# dualAudio2GatewithCV.net
KiCad netlist of a schematic drawn in EAGLE
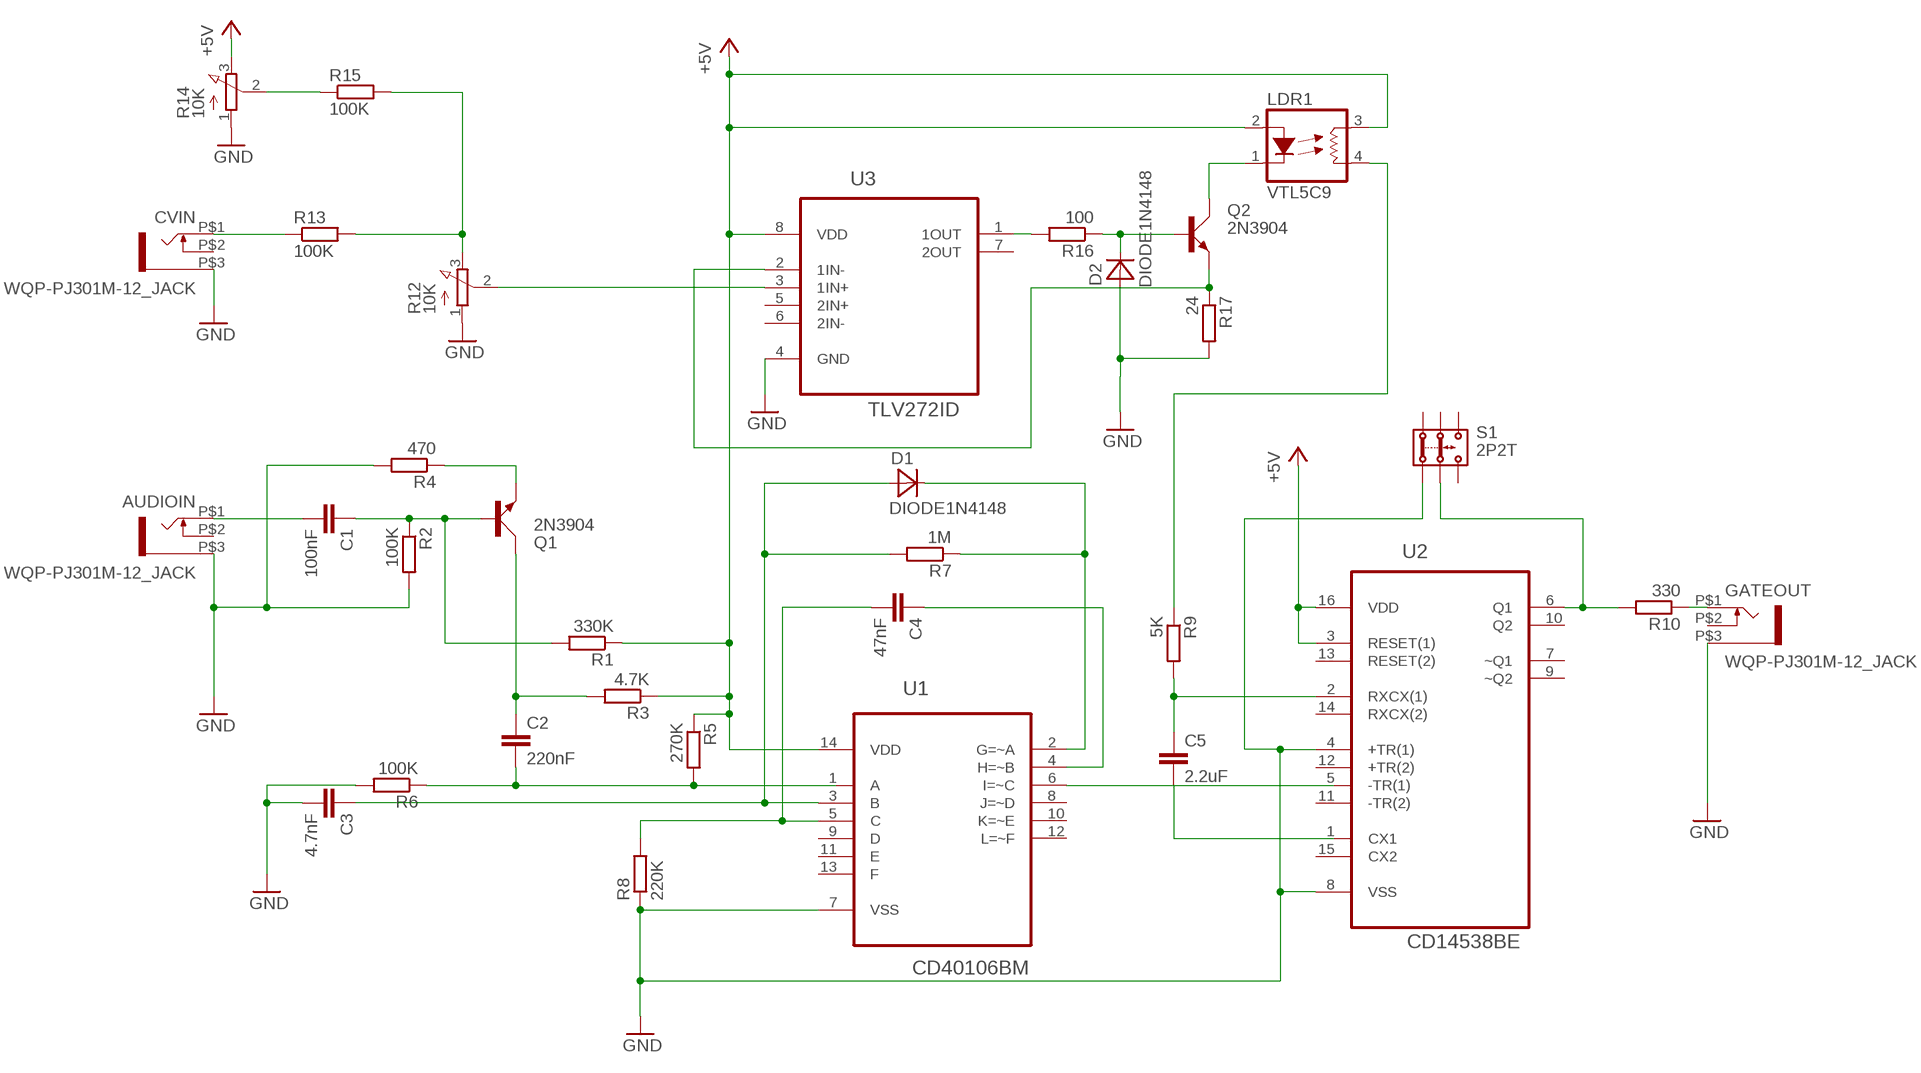
[diagram p0: schematic, sheet 1]

(export (version "E")
  (design (tool "Eeschema 10.0.6"))
  (components
    (comp (ref "AUDIOIN")
      (value "WQP-PJ301M-12_JACK")
      (footprint "eagle-import:WQP-PJ301M-12_JACK")
      (libsource (lib "eagle-import") (part "WQP-PJ301M-12_JACK"))
    )
    (comp (ref "C1")
      (value "100nF")
      (footprint "eagle-import:C025-025X050")
      (libsource (lib "eagle-import") (part "C-EU025-025X050"))
    )
    (comp (ref "C2")
      (value "220nF")
      (footprint "eagle-import:C025-025X050")
      (libsource (lib "eagle-import") (part "C-EU025-025X050"))
    )
    (comp (ref "C3")
      (value "4.7nF")
      (footprint "eagle-import:C025-025X050")
      (libsource (lib "eagle-import") (part "C-EU025-025X050"))
    )
    (comp (ref "C4")
      (value "47nF")
      (footprint "eagle-import:C025-025X050")
      (libsource (lib "eagle-import") (part "C-EU025-025X050"))
    )
    (comp (ref "C5")
      (value "2.2uF")
      (footprint "eagle-import:C025-025X050")
      (libsource (lib "eagle-import") (part "C-EU025-025X050"))
    )
    (comp (ref "CVIN")
      (value "WQP-PJ301M-12_JACK")
      (footprint "eagle-import:WQP-PJ301M-12_JACK")
      (libsource (lib "eagle-import") (part "WQP-PJ301M-12_JACK"))
    )
    (comp (ref "D1")
      (value "DIODE1N4148")
      (footprint "eagle-import:DO-35")
      (libsource (lib "eagle-import") (part "DIODE1N4148"))
    )
    (comp (ref "D2")
      (value "DIODE1N4148")
      (footprint "eagle-import:DO-35")
      (libsource (lib "eagle-import") (part "DIODE1N4148"))
    )
    (comp (ref "GATEOUT")
      (value "WQP-PJ301M-12_JACK")
      (footprint "eagle-import:WQP-PJ301M-12_JACK")
      (libsource (lib "eagle-import") (part "WQP-PJ301M-12_JACK"))
    )
    (comp (ref "LDR1")
      (value "VTL5C9")
      (footprint "eagle-import:VTL5C")
      (fields (field (name "MF") "VACTEC PHOTO"))
      (libsource (lib "eagle-import") (part "VTL5C9"))
    )
    (comp (ref "Q1")
      (value "2N3904")
      (footprint "eagle-import:TO92D")
      (libsource (lib "eagle-import") (part "2N3904"))
    )
    (comp (ref "Q2")
      (value "2N3904")
      (footprint "eagle-import:TO92D")
      (libsource (lib "eagle-import") (part "2N3904"))
    )
    (comp (ref "R1")
      (value "330K")
      (footprint "eagle-import:0204V")
      (libsource (lib "eagle-import") (part "R-EU_0204/2V"))
    )
    (comp (ref "R2")
      (value "100K")
      (footprint "eagle-import:0204V")
      (libsource (lib "eagle-import") (part "R-EU_0204/2V"))
    )
    (comp (ref "R3")
      (value "4.7K")
      (footprint "eagle-import:0204V")
      (libsource (lib "eagle-import") (part "R-EU_0204/2V"))
    )
    (comp (ref "R4")
      (value "470")
      (footprint "eagle-import:0204V")
      (libsource (lib "eagle-import") (part "R-EU_0204/2V"))
    )
    (comp (ref "R5")
      (value "270K")
      (footprint "eagle-import:0204V")
      (libsource (lib "eagle-import") (part "R-EU_0204/2V"))
    )
    (comp (ref "R6")
      (value "100K")
      (footprint "eagle-import:0204V")
      (libsource (lib "eagle-import") (part "R-EU_0204/2V"))
    )
    (comp (ref "R7")
      (value "1M")
      (footprint "eagle-import:0204V")
      (libsource (lib "eagle-import") (part "R-EU_0204/2V"))
    )
    (comp (ref "R8")
      (value "220K")
      (footprint "eagle-import:0204V")
      (libsource (lib "eagle-import") (part "R-EU_0204/2V"))
    )
    (comp (ref "R9")
      (value "5K")
      (footprint "eagle-import:0204V")
      (libsource (lib "eagle-import") (part "R-EU_0204/2V"))
    )
    (comp (ref "R10")
      (value "330")
      (footprint "eagle-import:0204V")
      (libsource (lib "eagle-import") (part "R-EU_0204/2V"))
    )
    (comp (ref "R12")
      (value "10K")
      (footprint "eagle-import:3RP_1610N")
      (libsource (lib "eagle-import") (part "3RP/1610N"))
    )
    (comp (ref "R13")
      (value "100K")
      (footprint "eagle-import:0204V")
      (libsource (lib "eagle-import") (part "R-EU_0204/2V"))
    )
    (comp (ref "R14")
      (value "10K")
      (footprint "eagle-import:3RP_1610N")
      (libsource (lib "eagle-import") (part "3RP/1610N"))
    )
    (comp (ref "R15")
      (value "100K")
      (footprint "eagle-import:0204V")
      (libsource (lib "eagle-import") (part "R-EU_0204/2V"))
    )
    (comp (ref "R16")
      (value "100")
      (footprint "eagle-import:0204V")
      (libsource (lib "eagle-import") (part "R-EU_0204/2V"))
    )
    (comp (ref "R17")
      (value "24")
      (footprint "eagle-import:0204V")
      (libsource (lib "eagle-import") (part "R-EU_0204/2V"))
    )
    (comp (ref "S1")
      (value "2P2T")
      (footprint "eagle-import:2P2T")
      (libsource (lib "eagle-import") (part "2P2T"))
    )
    (comp (ref "U1")
      (value "CD40106BM")
      (footprint "eagle-import:SOIC127P600X175-14N")
      (libsource (lib "eagle-import") (part "CD40106BM"))
    )
    (comp (ref "U2")
      (value "CD14538BE")
      (footprint "eagle-import:DIP254P762X508-16")
      (libsource (lib "eagle-import") (part "CD14538BE"))
    )
    (comp (ref "U3")
      (value "TLV272ID")
      (footprint "eagle-import:SOIC127P600X175-8N")
      (libsource (lib "eagle-import") (part "TLV272ID"))
    )
  )
  (nets
    (net (code "1") (name "+5V") (class "Default")
      (node (ref "LDR1") (pin "2") (pinfunction "A_2") (pintype "passive"))
      (node (ref "LDR1") (pin "3") (pinfunction "L1_3") (pintype "passive"))
      (node (ref "R1") (pin "1") (pinfunction "1_1") (pintype "passive"))
      (node (ref "R14") (pin "3") (pinfunction "E_3") (pintype "passive"))
      (node (ref "R3") (pin "1") (pinfunction "1_1") (pintype "passive"))
      (node (ref "R5") (pin "1") (pinfunction "1_1") (pintype "passive"))
      (node (ref "U1") (pin "14") (pinfunction "VDD_14") (pintype "power_in"))
      (node (ref "U2") (pin "16") (pinfunction "VDD_16") (pintype "power_in"))
      (node (ref "U2") (pin "3") (pinfunction "RESET(1)_3") (pintype "input"))
      (node (ref "U3") (pin "8") (pinfunction "VDD_8") (pintype "power_in"))
    )
    (net (code "2") (name "GND") (class "Default")
      (node (ref "AUDIOIN") (pin "P$3") (pinfunction "1_P$3") (pintype "passive"))
      (node (ref "C3") (pin "2") (pinfunction "2_2") (pintype "passive"))
      (node (ref "CVIN") (pin "P$3") (pinfunction "1_P$3") (pintype "passive"))
      (node (ref "D2") (pin "+") (pinfunction "+_+") (pintype "passive"))
      (node (ref "GATEOUT") (pin "P$3") (pinfunction "1_P$3") (pintype "passive"))
      (node (ref "R12") (pin "1") (pinfunction "A_1") (pintype "passive"))
      (node (ref "R14") (pin "1") (pinfunction "A_1") (pintype "passive"))
      (node (ref "R17") (pin "2") (pinfunction "2_2") (pintype "passive"))
      (node (ref "R2") (pin "2") (pinfunction "2_2") (pintype "passive"))
      (node (ref "R4") (pin "2") (pinfunction "2_2") (pintype "passive"))
      (node (ref "R6") (pin "2") (pinfunction "2_2") (pintype "passive"))
      (node (ref "R8") (pin "1") (pinfunction "1_1") (pintype "passive"))
      (node (ref "S1") (pin "1.2") (pinfunction "1.2_1.2") (pintype "passive"))
      (node (ref "U1") (pin "7") (pinfunction "VSS_7") (pintype "power_in"))
      (node (ref "U2") (pin "4") (pinfunction "+TR(1)_4") (pintype "input"))
      (node (ref "U2") (pin "8") (pinfunction "VSS_8") (pintype "power_in"))
      (node (ref "U3") (pin "4") (pinfunction "GND_4") (pintype "passive"))
    )
    (net (code "3") (name "Net-(AUDIOIN-2)") (class "Default")
      (node (ref "AUDIOIN") (pin "P$1") (pinfunction "2_P$1") (pintype "passive"))
      (node (ref "C1") (pin "2") (pinfunction "2_2") (pintype "passive"))
    )
    (net (code "4") (name "Net-(C1-Pad1)") (class "Default")
      (node (ref "C1") (pin "1") (pinfunction "1_1") (pintype "passive"))
      (node (ref "Q1") (pin "B") (pinfunction "B_B") (pintype "passive"))
      (node (ref "R1") (pin "2") (pinfunction "2_2") (pintype "passive"))
      (node (ref "R2") (pin "1") (pinfunction "1_1") (pintype "passive"))
    )
    (net (code "5") (name "Net-(C2-Pad1)") (class "Default")
      (node (ref "C2") (pin "1") (pinfunction "1_1") (pintype "passive"))
      (node (ref "Q1") (pin "C") (pinfunction "C_C") (pintype "passive"))
      (node (ref "R3") (pin "2") (pinfunction "2_2") (pintype "passive"))
    )
    (net (code "6") (name "Net-(C2-Pad2)") (class "Default")
      (node (ref "C2") (pin "2") (pinfunction "2_2") (pintype "passive"))
      (node (ref "R5") (pin "2") (pinfunction "2_2") (pintype "passive"))
      (node (ref "R6") (pin "1") (pinfunction "1_1") (pintype "passive"))
    )
    (net (code "7") (name "Net-(CVIN-2)") (class "Default")
      (node (ref "CVIN") (pin "P$1") (pinfunction "2_P$1") (pintype "passive"))
      (node (ref "R13") (pin "1") (pinfunction "1_1") (pintype "passive"))
    )
    (net (code "8") (name "Net-(D2-Pad-)") (class "Default")
      (node (ref "D2") (pin "-") (pinfunction "-_-") (pintype "passive"))
      (node (ref "Q2") (pin "B") (pinfunction "B_B") (pintype "passive"))
      (node (ref "R16") (pin "1") (pinfunction "1_1") (pintype "passive"))
    )
    (net (code "9") (name "Net-(GATEOUT-2)") (class "Default")
      (node (ref "GATEOUT") (pin "P$1") (pinfunction "2_P$1") (pintype "passive"))
      (node (ref "R10") (pin "1") (pinfunction "1_1") (pintype "passive"))
    )
    (net (code "10") (name "Net-(LDR1-C)") (class "Default")
      (node (ref "LDR1") (pin "1") (pinfunction "C_1") (pintype "passive"))
      (node (ref "Q2") (pin "C") (pinfunction "C_C") (pintype "passive"))
    )
    (net (code "11") (name "Net-(LDR1-L2)") (class "Default")
      (node (ref "LDR1") (pin "4") (pinfunction "L2_4") (pintype "passive"))
      (node (ref "R9") (pin "1") (pinfunction "1_1") (pintype "passive"))
    )
    (net (code "12") (name "Net-(Q1-PadE)") (class "Default")
      (node (ref "Q1") (pin "E") (pinfunction "E_E") (pintype "passive"))
      (node (ref "R4") (pin "1") (pinfunction "1_1") (pintype "passive"))
    )
    (net (code "13") (name "Net-(R12-E)") (class "Default")
      (node (ref "R12") (pin "3") (pinfunction "E_3") (pintype "passive"))
      (node (ref "R13") (pin "2") (pinfunction "2_2") (pintype "passive"))
      (node (ref "R15") (pin "2") (pinfunction "2_2") (pintype "passive"))
    )
    (net (code "14") (name "Net-(R12-S)") (class "Default")
      (node (ref "R12") (pin "2") (pinfunction "S_2") (pintype "passive"))
      (node (ref "U3") (pin "3") (pinfunction "1IN+_3") (pintype "input"))
    )
    (net (code "15") (name "Net-(R14-S)") (class "Default")
      (node (ref "R14") (pin "2") (pinfunction "S_2") (pintype "passive"))
      (node (ref "R15") (pin "1") (pinfunction "1_1") (pintype "passive"))
    )
    (net (code "16") (name "Net-(U1-B)") (class "Default")
      (node (ref "C3") (pin "1") (pinfunction "1_1") (pintype "passive"))
      (node (ref "D1") (pin "+") (pinfunction "+_+") (pintype "passive"))
      (node (ref "R7") (pin "2") (pinfunction "2_2") (pintype "passive"))
      (node (ref "U1") (pin "3") (pinfunction "B_3") (pintype "input"))
    )
    (net (code "17") (name "Net-(U1-C)") (class "Default")
      (node (ref "C4") (pin "2") (pinfunction "2_2") (pintype "passive"))
      (node (ref "R8") (pin "2") (pinfunction "2_2") (pintype "passive"))
      (node (ref "U1") (pin "5") (pinfunction "C_5") (pintype "input"))
    )
    (net (code "18") (name "Net-(U1-G=~{A})") (class "Default")
      (node (ref "D1") (pin "-") (pinfunction "-_-") (pintype "passive"))
      (node (ref "R7") (pin "1") (pinfunction "1_1") (pintype "passive"))
      (node (ref "U1") (pin "2") (pinfunction "G=~{A}_2") (pintype "output"))
    )
    (net (code "19") (name "Net-(U1-H=~{B})") (class "Default")
      (node (ref "C4") (pin "1") (pinfunction "1_1") (pintype "passive"))
      (node (ref "U1") (pin "4") (pinfunction "H=~{B}_4") (pintype "output"))
    )
    (net (code "20") (name "Net-(U1-I=~{C})") (class "Default")
      (node (ref "U1") (pin "6") (pinfunction "I=~{C}_6") (pintype "output"))
      (node (ref "U2") (pin "5") (pinfunction "-TR(1)_5") (pintype "input"))
    )
    (net (code "21") (name "Net-(U2-CX1)") (class "Default")
      (node (ref "C5") (pin "2") (pinfunction "2_2") (pintype "passive"))
      (node (ref "U2") (pin "1") (pinfunction "CX1_1") (pintype "input"))
    )
    (net (code "22") (name "Net-(U2-Q1)") (class "Default")
      (node (ref "R10") (pin "2") (pinfunction "2_2") (pintype "passive"))
      (node (ref "S1") (pin "2.2") (pinfunction "2.2_2.2") (pintype "passive"))
      (node (ref "U2") (pin "6") (pinfunction "Q1_6") (pintype "output"))
    )
    (net (code "23") (name "Net-(U2-RXCX(1))") (class "Default")
      (node (ref "C5") (pin "1") (pinfunction "1_1") (pintype "passive"))
      (node (ref "R9") (pin "2") (pinfunction "2_2") (pintype "passive"))
      (node (ref "U2") (pin "2") (pinfunction "RXCX(1)_2") (pintype "input"))
    )
    (net (code "24") (name "Net-(U3-1IN-)") (class "Default")
      (node (ref "Q2") (pin "E") (pinfunction "E_E") (pintype "passive"))
      (node (ref "R17") (pin "1") (pinfunction "1_1") (pintype "passive"))
      (node (ref "U3") (pin "2") (pinfunction "1IN-_2") (pintype "input"))
    )
    (net (code "25") (name "Net-(U3-1OUT)") (class "Default")
      (node (ref "R16") (pin "2") (pinfunction "2_2") (pintype "passive"))
      (node (ref "U3") (pin "1") (pinfunction "1OUT_1") (pintype "output"))
    )
    (net (code "26") (name "unconnected-(AUDIOIN-3-PadP$2)") (class "Default")
      (node (ref "AUDIOIN") (pin "P$2") (pinfunction "3_P$2") (pintype "passive"))
    )
    (net (code "27") (name "unconnected-(CVIN-3-PadP$2)") (class "Default")
      (node (ref "CVIN") (pin "P$2") (pinfunction "3_P$2") (pintype "passive"))
    )
    (net (code "28") (name "unconnected-(GATEOUT-3-PadP$2)") (class "Default")
      (node (ref "GATEOUT") (pin "P$2") (pinfunction "3_P$2") (pintype "passive"))
    )
    (net (code "29") (name "unconnected-(S1-Pad1.1)") (class "Default")
      (node (ref "S1") (pin "1.1") (pinfunction "1.1_1.1") (pintype "passive"))
    )
    (net (code "30") (name "unconnected-(S1-Pad2.1)") (class "Default")
      (node (ref "S1") (pin "2.1") (pinfunction "2.1_2.1") (pintype "passive"))
    )
    (net (code "31") (name "unconnected-(S1-Pad3.1)") (class "Default")
      (node (ref "S1") (pin "3.1") (pinfunction "3.1_3.1") (pintype "passive"))
    )
    (net (code "32") (name "unconnected-(S1-Pad3.2)") (class "Default")
      (node (ref "S1") (pin "3.2") (pinfunction "3.2_3.2") (pintype "passive"))
    )
    (net (code "33") (name "unconnected-(U1-A-Pad1)") (class "Default")
      (node (ref "U1") (pin "1") (pinfunction "A_1") (pintype "input"))
    )
    (net (code "34") (name "unconnected-(U1-D-Pad9)") (class "Default")
      (node (ref "U1") (pin "9") (pinfunction "D_9") (pintype "input"))
    )
    (net (code "35") (name "unconnected-(U1-E-Pad11)") (class "Default")
      (node (ref "U1") (pin "11") (pinfunction "E_11") (pintype "input"))
    )
    (net (code "36") (name "unconnected-(U1-F-Pad13)") (class "Default")
      (node (ref "U1") (pin "13") (pinfunction "F_13") (pintype "input"))
    )
    (net (code "37") (name "unconnected-(U1-J=~{D}-Pad8)") (class "Default")
      (node (ref "U1") (pin "8") (pinfunction "J=~{D}_8") (pintype "output"))
    )
    (net (code "38") (name "unconnected-(U1-K=~{E}-Pad10)") (class "Default")
      (node (ref "U1") (pin "10") (pinfunction "K=~{E}_10") (pintype "output"))
    )
    (net (code "39") (name "unconnected-(U1-L=~{F}-Pad12)") (class "Default")
      (node (ref "U1") (pin "12") (pinfunction "L=~{F}_12") (pintype "output"))
    )
    (net (code "40") (name "unconnected-(U2-+TR(2)-Pad12)") (class "Default")
      (node (ref "U2") (pin "12") (pinfunction "+TR(2)_12") (pintype "input"))
    )
    (net (code "41") (name "unconnected-(U2--TR(2)-Pad11)") (class "Default")
      (node (ref "U2") (pin "11") (pinfunction "-TR(2)_11") (pintype "input"))
    )
    (net (code "42") (name "unconnected-(U2-CX2-Pad15)") (class "Default")
      (node (ref "U2") (pin "15") (pinfunction "CX2_15") (pintype "input"))
    )
    (net (code "43") (name "unconnected-(U2-Q2-Pad10)") (class "Default")
      (node (ref "U2") (pin "10") (pinfunction "Q2_10") (pintype "output"))
    )
    (net (code "44") (name "unconnected-(U2-RESET(2)-Pad13)") (class "Default")
      (node (ref "U2") (pin "13") (pinfunction "RESET(2)_13") (pintype "input"))
    )
    (net (code "45") (name "unconnected-(U2-RXCX(2)-Pad14)") (class "Default")
      (node (ref "U2") (pin "14") (pinfunction "RXCX(2)_14") (pintype "input"))
    )
    (net (code "46") (name "unconnected-(U2-~{Q1}-Pad7)") (class "Default")
      (node (ref "U2") (pin "7") (pinfunction "~{Q1}_7") (pintype "output"))
    )
    (net (code "47") (name "unconnected-(U2-~{Q2}-Pad9)") (class "Default")
      (node (ref "U2") (pin "9") (pinfunction "~{Q2}_9") (pintype "output"))
    )
    (net (code "48") (name "unconnected-(U3-2IN+-Pad5)") (class "Default")
      (node (ref "U3") (pin "5") (pinfunction "2IN+_5") (pintype "input"))
    )
    (net (code "49") (name "unconnected-(U3-2IN--Pad6)") (class "Default")
      (node (ref "U3") (pin "6") (pinfunction "2IN-_6") (pintype "input"))
    )
    (net (code "50") (name "unconnected-(U3-2OUT-Pad7)") (class "Default")
      (node (ref "U3") (pin "7") (pinfunction "2OUT_7") (pintype "output"))
    )
  )
)
